# dmx_splitter.net
KiCad netlist of a schematic drawn in EAGLE
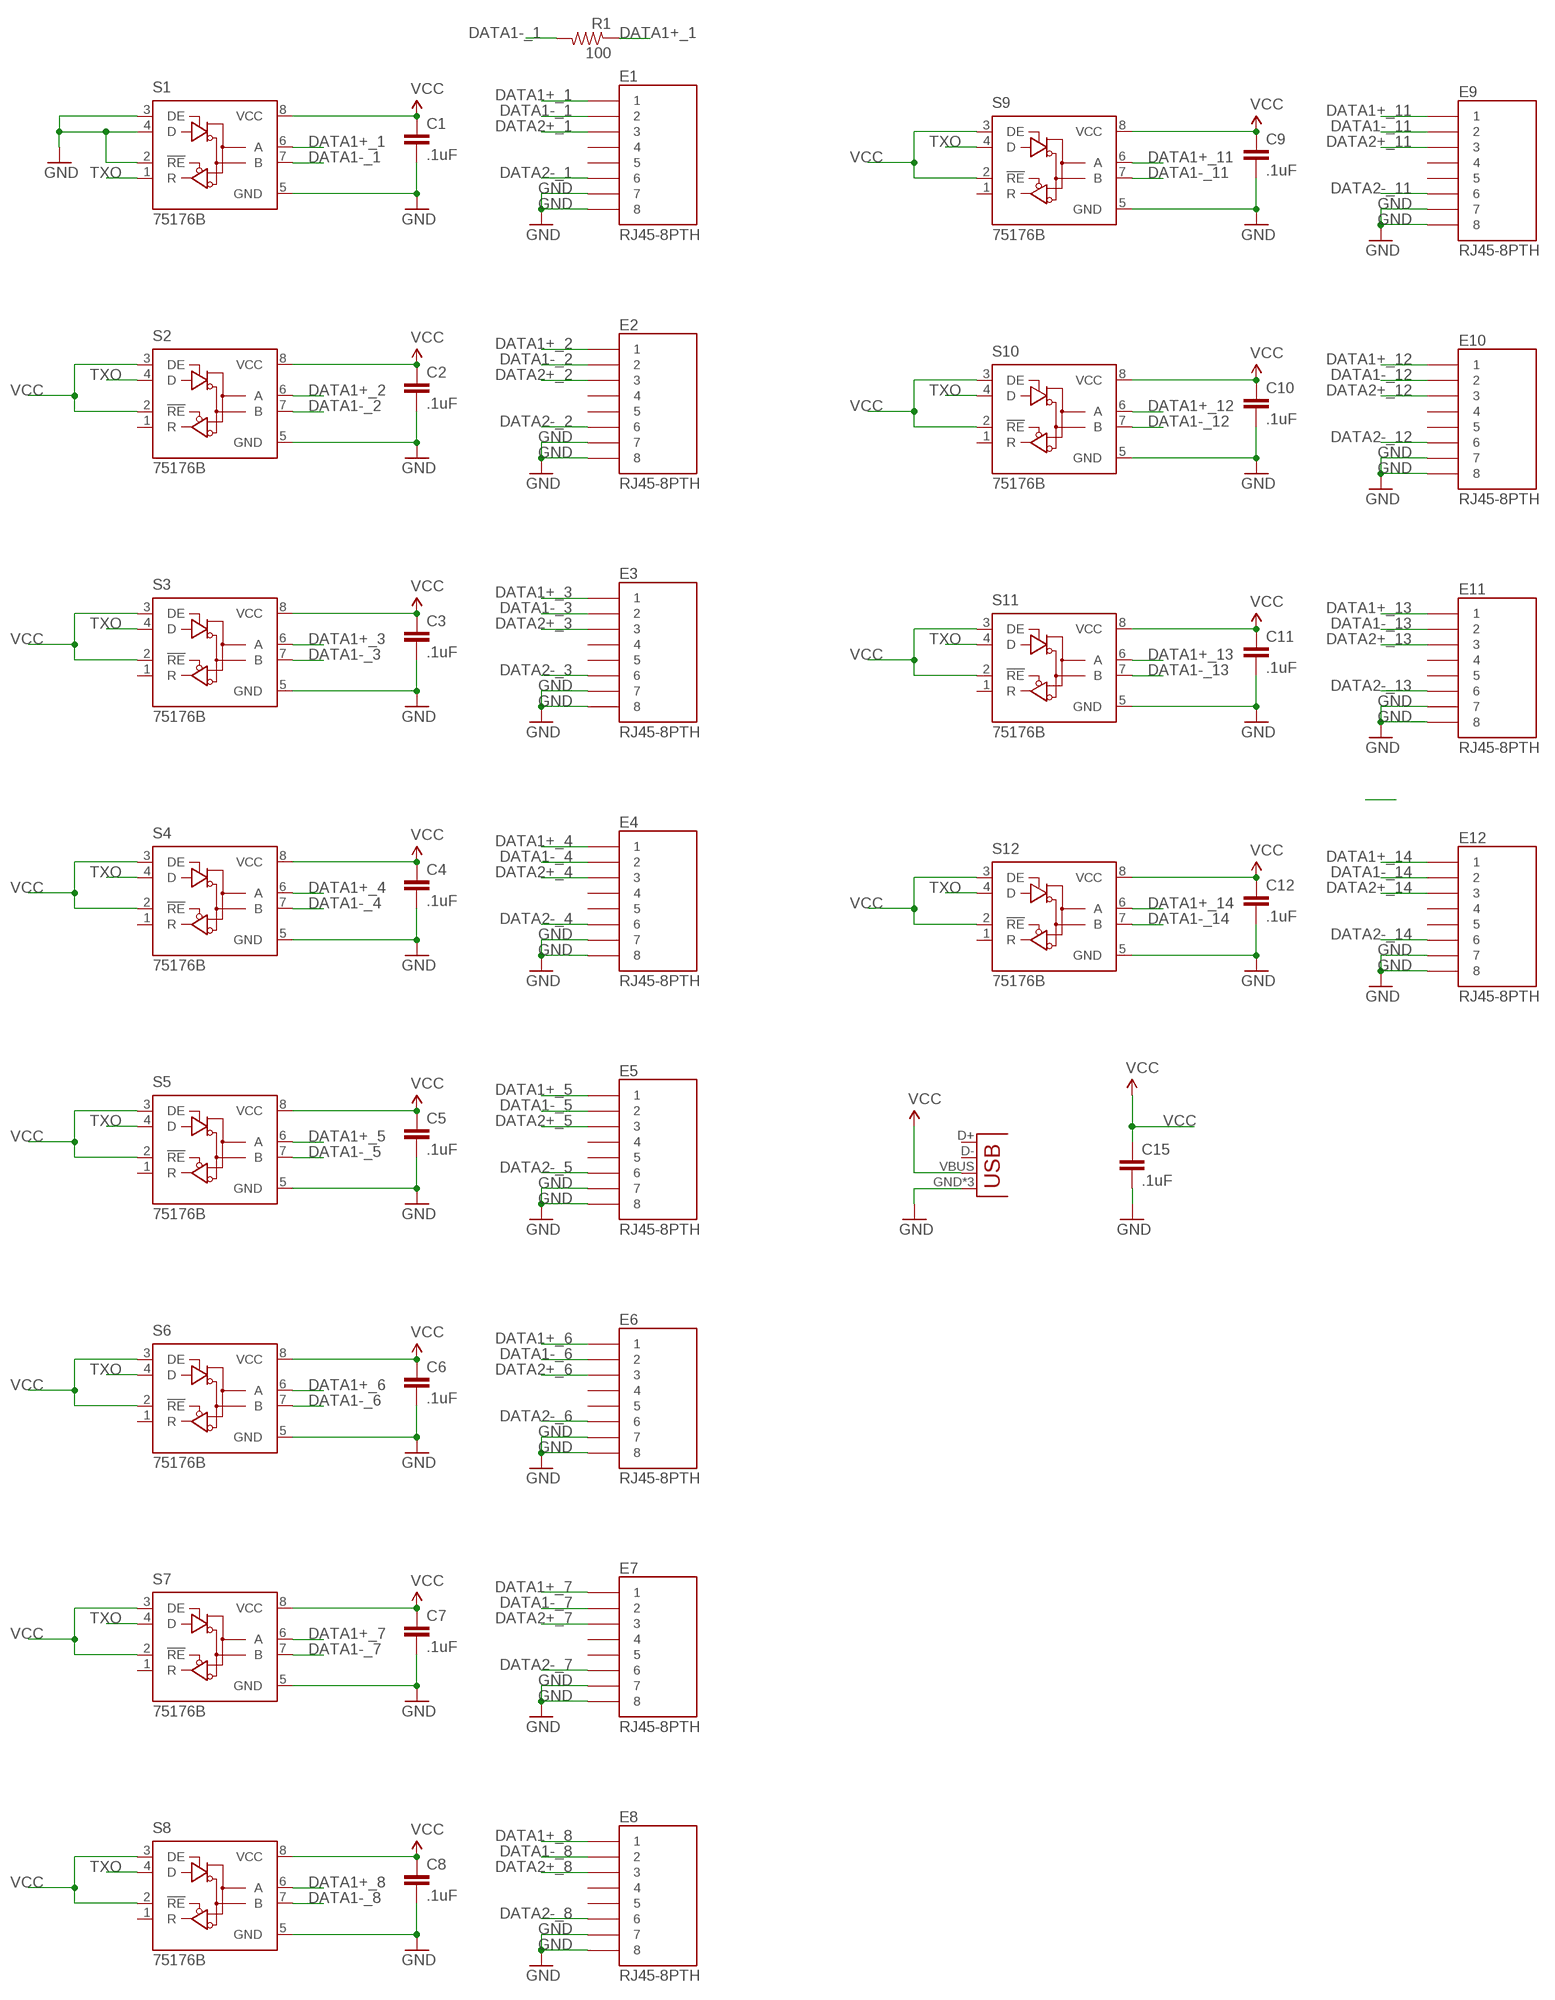
[diagram p0: schematic, sheet 1]

(export (version "E")
  (design (tool "Eeschema 10.0.6"))
  (components
    (comp (ref "C1")
      (value ".1uF")
      (footprint "eagle-import:0402-CAP")
      (libsource (lib "eagle-import") (part "CAP0402-CAP"))
    )
    (comp (ref "C2")
      (value ".1uF")
      (footprint "eagle-import:0402-CAP")
      (libsource (lib "eagle-import") (part "CAP0402-CAP"))
    )
    (comp (ref "C3")
      (value ".1uF")
      (footprint "eagle-import:0402-CAP")
      (libsource (lib "eagle-import") (part "CAP0402-CAP"))
    )
    (comp (ref "C4")
      (value ".1uF")
      (footprint "eagle-import:0402-CAP")
      (libsource (lib "eagle-import") (part "CAP0402-CAP"))
    )
    (comp (ref "C5")
      (value ".1uF")
      (footprint "eagle-import:0402-CAP")
      (libsource (lib "eagle-import") (part "CAP0402-CAP"))
    )
    (comp (ref "C6")
      (value ".1uF")
      (footprint "eagle-import:0402-CAP")
      (libsource (lib "eagle-import") (part "CAP0402-CAP"))
    )
    (comp (ref "C7")
      (value ".1uF")
      (footprint "eagle-import:0402-CAP")
      (libsource (lib "eagle-import") (part "CAP0402-CAP"))
    )
    (comp (ref "C8")
      (value ".1uF")
      (footprint "eagle-import:0402-CAP")
      (libsource (lib "eagle-import") (part "CAP0402-CAP"))
    )
    (comp (ref "C9")
      (value ".1uF")
      (footprint "eagle-import:0402-CAP")
      (libsource (lib "eagle-import") (part "CAP0402-CAP"))
    )
    (comp (ref "C10")
      (value ".1uF")
      (footprint "eagle-import:0402-CAP")
      (libsource (lib "eagle-import") (part "CAP0402-CAP"))
    )
    (comp (ref "C11")
      (value ".1uF")
      (footprint "eagle-import:0402-CAP")
      (libsource (lib "eagle-import") (part "CAP0402-CAP"))
    )
    (comp (ref "C12")
      (value ".1uF")
      (footprint "eagle-import:0402-CAP")
      (libsource (lib "eagle-import") (part "CAP0402-CAP"))
    )
    (comp (ref "C15")
      (value ".1uF")
      (footprint "eagle-import:0402-CAP")
      (libsource (lib "eagle-import") (part "CAP0402-CAP"))
    )
    (comp (ref "E1")
      (value "RJ45-8PTH")
      (footprint "eagle-import:RJ45-8")
      (libsource (lib "eagle-import") (part "RJ45-8PTH"))
    )
    (comp (ref "E2")
      (value "RJ45-8PTH")
      (footprint "eagle-import:RJ45-8")
      (libsource (lib "eagle-import") (part "RJ45-8PTH"))
    )
    (comp (ref "E3")
      (value "RJ45-8PTH")
      (footprint "eagle-import:RJ45-8")
      (libsource (lib "eagle-import") (part "RJ45-8PTH"))
    )
    (comp (ref "E4")
      (value "RJ45-8PTH")
      (footprint "eagle-import:RJ45-8")
      (libsource (lib "eagle-import") (part "RJ45-8PTH"))
    )
    (comp (ref "E5")
      (value "RJ45-8PTH")
      (footprint "eagle-import:RJ45-8")
      (libsource (lib "eagle-import") (part "RJ45-8PTH"))
    )
    (comp (ref "E6")
      (value "RJ45-8PTH")
      (footprint "eagle-import:RJ45-8")
      (libsource (lib "eagle-import") (part "RJ45-8PTH"))
    )
    (comp (ref "E7")
      (value "RJ45-8PTH")
      (footprint "eagle-import:RJ45-8")
      (libsource (lib "eagle-import") (part "RJ45-8PTH"))
    )
    (comp (ref "E8")
      (value "RJ45-8PTH")
      (footprint "eagle-import:RJ45-8")
      (libsource (lib "eagle-import") (part "RJ45-8PTH"))
    )
    (comp (ref "E9")
      (value "RJ45-8PTH")
      (footprint "eagle-import:RJ45-8")
      (libsource (lib "eagle-import") (part "RJ45-8PTH"))
    )
    (comp (ref "E10")
      (value "RJ45-8PTH")
      (footprint "eagle-import:RJ45-8")
      (libsource (lib "eagle-import") (part "RJ45-8PTH"))
    )
    (comp (ref "E11")
      (value "RJ45-8PTH")
      (footprint "eagle-import:RJ45-8")
      (libsource (lib "eagle-import") (part "RJ45-8PTH"))
    )
    (comp (ref "E12")
      (value "RJ45-8PTH")
      (footprint "eagle-import:RJ45-8")
      (libsource (lib "eagle-import") (part "RJ45-8PTH"))
    )
    (comp (ref "JP1")
      (value "USB-MICROB")
      (footprint "eagle-import:USB-MICROB")
      (libsource (lib "eagle-import") (part "USB-MICROB"))
    )
    (comp (ref "R1")
      (value "100")
      (footprint "eagle-import:1206")
      (libsource (lib "eagle-import") (part "RESISTOR1206"))
    )
    (comp (ref "S1")
      (value "75176B")
      (footprint "eagle-import:D_R-PDSO-G8")
      (libsource (lib "eagle-import") (part "75176B"))
    )
    (comp (ref "S2")
      (value "75176B")
      (footprint "eagle-import:D_R-PDSO-G8")
      (libsource (lib "eagle-import") (part "75176B"))
    )
    (comp (ref "S3")
      (value "75176B")
      (footprint "eagle-import:D_R-PDSO-G8")
      (libsource (lib "eagle-import") (part "75176B"))
    )
    (comp (ref "S4")
      (value "75176B")
      (footprint "eagle-import:D_R-PDSO-G8")
      (libsource (lib "eagle-import") (part "75176B"))
    )
    (comp (ref "S5")
      (value "75176B")
      (footprint "eagle-import:D_R-PDSO-G8")
      (libsource (lib "eagle-import") (part "75176B"))
    )
    (comp (ref "S6")
      (value "75176B")
      (footprint "eagle-import:D_R-PDSO-G8")
      (libsource (lib "eagle-import") (part "75176B"))
    )
    (comp (ref "S7")
      (value "75176B")
      (footprint "eagle-import:D_R-PDSO-G8")
      (libsource (lib "eagle-import") (part "75176B"))
    )
    (comp (ref "S8")
      (value "75176B")
      (footprint "eagle-import:D_R-PDSO-G8")
      (libsource (lib "eagle-import") (part "75176B"))
    )
    (comp (ref "S9")
      (value "75176B")
      (footprint "eagle-import:D_R-PDSO-G8")
      (libsource (lib "eagle-import") (part "75176B"))
    )
    (comp (ref "S10")
      (value "75176B")
      (footprint "eagle-import:D_R-PDSO-G8")
      (libsource (lib "eagle-import") (part "75176B"))
    )
    (comp (ref "S11")
      (value "75176B")
      (footprint "eagle-import:D_R-PDSO-G8")
      (libsource (lib "eagle-import") (part "75176B"))
    )
    (comp (ref "S12")
      (value "75176B")
      (footprint "eagle-import:D_R-PDSO-G8")
      (libsource (lib "eagle-import") (part "75176B"))
    )
  )
  (nets
    (net (code "1") (name "/DATA1+_1") (class "Default")
      (node (ref "E1") (pin "1") (pinfunction "1_1") (pintype "bidirectional"))
      (node (ref "R1") (pin "1") (pinfunction "1_1") (pintype "passive"))
      (node (ref "S1") (pin "6") (pinfunction "A_6") (pintype "output"))
    )
    (net (code "2") (name "/DATA1+_2") (class "Default")
      (node (ref "E2") (pin "1") (pinfunction "1_1") (pintype "bidirectional"))
      (node (ref "S2") (pin "6") (pinfunction "A_6") (pintype "output"))
    )
    (net (code "3") (name "/DATA1+_3") (class "Default")
      (node (ref "E3") (pin "1") (pinfunction "1_1") (pintype "bidirectional"))
      (node (ref "S3") (pin "6") (pinfunction "A_6") (pintype "output"))
    )
    (net (code "4") (name "/DATA1+_4") (class "Default")
      (node (ref "E4") (pin "1") (pinfunction "1_1") (pintype "bidirectional"))
      (node (ref "S4") (pin "6") (pinfunction "A_6") (pintype "output"))
    )
    (net (code "5") (name "/DATA1+_5") (class "Default")
      (node (ref "E5") (pin "1") (pinfunction "1_1") (pintype "bidirectional"))
      (node (ref "S5") (pin "6") (pinfunction "A_6") (pintype "output"))
    )
    (net (code "6") (name "/DATA1+_6") (class "Default")
      (node (ref "E6") (pin "1") (pinfunction "1_1") (pintype "bidirectional"))
      (node (ref "S6") (pin "6") (pinfunction "A_6") (pintype "output"))
    )
    (net (code "7") (name "/DATA1+_7") (class "Default")
      (node (ref "E7") (pin "1") (pinfunction "1_1") (pintype "bidirectional"))
      (node (ref "S7") (pin "6") (pinfunction "A_6") (pintype "output"))
    )
    (net (code "8") (name "/DATA1+_8") (class "Default")
      (node (ref "E8") (pin "1") (pinfunction "1_1") (pintype "bidirectional"))
      (node (ref "S8") (pin "6") (pinfunction "A_6") (pintype "output"))
    )
    (net (code "9") (name "/DATA1+_11") (class "Default")
      (node (ref "E9") (pin "1") (pinfunction "1_1") (pintype "bidirectional"))
      (node (ref "S9") (pin "6") (pinfunction "A_6") (pintype "output"))
    )
    (net (code "10") (name "/DATA1+_12") (class "Default")
      (node (ref "E10") (pin "1") (pinfunction "1_1") (pintype "bidirectional"))
      (node (ref "S10") (pin "6") (pinfunction "A_6") (pintype "output"))
    )
    (net (code "11") (name "/DATA1+_13") (class "Default")
      (node (ref "E11") (pin "1") (pinfunction "1_1") (pintype "bidirectional"))
      (node (ref "S11") (pin "6") (pinfunction "A_6") (pintype "output"))
    )
    (net (code "12") (name "/DATA1+_14") (class "Default")
      (node (ref "E12") (pin "1") (pinfunction "1_1") (pintype "bidirectional"))
      (node (ref "S12") (pin "6") (pinfunction "A_6") (pintype "output"))
    )
    (net (code "13") (name "/DATA1-_1") (class "Default")
      (node (ref "E1") (pin "2") (pinfunction "2_2") (pintype "bidirectional"))
      (node (ref "R1") (pin "2") (pinfunction "2_2") (pintype "passive"))
      (node (ref "S1") (pin "7") (pinfunction "B_7") (pintype "output"))
    )
    (net (code "14") (name "/DATA1-_2") (class "Default")
      (node (ref "E2") (pin "2") (pinfunction "2_2") (pintype "bidirectional"))
      (node (ref "S2") (pin "7") (pinfunction "B_7") (pintype "output"))
    )
    (net (code "15") (name "/DATA1-_3") (class "Default")
      (node (ref "E3") (pin "2") (pinfunction "2_2") (pintype "bidirectional"))
      (node (ref "S3") (pin "7") (pinfunction "B_7") (pintype "output"))
    )
    (net (code "16") (name "/DATA1-_4") (class "Default")
      (node (ref "E4") (pin "2") (pinfunction "2_2") (pintype "bidirectional"))
      (node (ref "S4") (pin "7") (pinfunction "B_7") (pintype "output"))
    )
    (net (code "17") (name "/DATA1-_5") (class "Default")
      (node (ref "E5") (pin "2") (pinfunction "2_2") (pintype "bidirectional"))
      (node (ref "S5") (pin "7") (pinfunction "B_7") (pintype "output"))
    )
    (net (code "18") (name "/DATA1-_6") (class "Default")
      (node (ref "E6") (pin "2") (pinfunction "2_2") (pintype "bidirectional"))
      (node (ref "S6") (pin "7") (pinfunction "B_7") (pintype "output"))
    )
    (net (code "19") (name "/DATA1-_7") (class "Default")
      (node (ref "E7") (pin "2") (pinfunction "2_2") (pintype "bidirectional"))
      (node (ref "S7") (pin "7") (pinfunction "B_7") (pintype "output"))
    )
    (net (code "20") (name "/DATA1-_8") (class "Default")
      (node (ref "E8") (pin "2") (pinfunction "2_2") (pintype "bidirectional"))
      (node (ref "S8") (pin "7") (pinfunction "B_7") (pintype "output"))
    )
    (net (code "21") (name "/DATA1-_11") (class "Default")
      (node (ref "E9") (pin "2") (pinfunction "2_2") (pintype "bidirectional"))
      (node (ref "S9") (pin "7") (pinfunction "B_7") (pintype "output"))
    )
    (net (code "22") (name "/DATA1-_12") (class "Default")
      (node (ref "E10") (pin "2") (pinfunction "2_2") (pintype "bidirectional"))
      (node (ref "S10") (pin "7") (pinfunction "B_7") (pintype "output"))
    )
    (net (code "23") (name "/DATA1-_13") (class "Default")
      (node (ref "E11") (pin "2") (pinfunction "2_2") (pintype "bidirectional"))
      (node (ref "S11") (pin "7") (pinfunction "B_7") (pintype "output"))
    )
    (net (code "24") (name "/DATA1-_14") (class "Default")
      (node (ref "E12") (pin "2") (pinfunction "2_2") (pintype "bidirectional"))
      (node (ref "S12") (pin "7") (pinfunction "B_7") (pintype "output"))
    )
    (net (code "25") (name "/DATA2+_1") (class "Default")
      (node (ref "E1") (pin "3") (pinfunction "3_3") (pintype "bidirectional"))
    )
    (net (code "26") (name "/DATA2+_2") (class "Default")
      (node (ref "E2") (pin "3") (pinfunction "3_3") (pintype "bidirectional"))
    )
    (net (code "27") (name "/DATA2+_3") (class "Default")
      (node (ref "E3") (pin "3") (pinfunction "3_3") (pintype "bidirectional"))
    )
    (net (code "28") (name "/DATA2+_4") (class "Default")
      (node (ref "E4") (pin "3") (pinfunction "3_3") (pintype "bidirectional"))
    )
    (net (code "29") (name "/DATA2+_5") (class "Default")
      (node (ref "E5") (pin "3") (pinfunction "3_3") (pintype "bidirectional"))
    )
    (net (code "30") (name "/DATA2+_6") (class "Default")
      (node (ref "E6") (pin "3") (pinfunction "3_3") (pintype "bidirectional"))
    )
    (net (code "31") (name "/DATA2+_7") (class "Default")
      (node (ref "E7") (pin "3") (pinfunction "3_3") (pintype "bidirectional"))
    )
    (net (code "32") (name "/DATA2+_8") (class "Default")
      (node (ref "E8") (pin "3") (pinfunction "3_3") (pintype "bidirectional"))
    )
    (net (code "33") (name "/DATA2+_11") (class "Default")
      (node (ref "E9") (pin "3") (pinfunction "3_3") (pintype "bidirectional"))
    )
    (net (code "34") (name "/DATA2+_12") (class "Default")
      (node (ref "E10") (pin "3") (pinfunction "3_3") (pintype "bidirectional"))
    )
    (net (code "35") (name "/DATA2+_13") (class "Default")
      (node (ref "E11") (pin "3") (pinfunction "3_3") (pintype "bidirectional"))
    )
    (net (code "36") (name "/DATA2+_14") (class "Default")
      (node (ref "E12") (pin "3") (pinfunction "3_3") (pintype "bidirectional"))
    )
    (net (code "37") (name "/DATA2-_1") (class "Default")
      (node (ref "E1") (pin "6") (pinfunction "6_6") (pintype "bidirectional"))
    )
    (net (code "38") (name "/DATA2-_2") (class "Default")
      (node (ref "E2") (pin "6") (pinfunction "6_6") (pintype "bidirectional"))
    )
    (net (code "39") (name "/DATA2-_3") (class "Default")
      (node (ref "E3") (pin "6") (pinfunction "6_6") (pintype "bidirectional"))
    )
    (net (code "40") (name "/DATA2-_4") (class "Default")
      (node (ref "E4") (pin "6") (pinfunction "6_6") (pintype "bidirectional"))
    )
    (net (code "41") (name "/DATA2-_5") (class "Default")
      (node (ref "E5") (pin "6") (pinfunction "6_6") (pintype "bidirectional"))
    )
    (net (code "42") (name "/DATA2-_6") (class "Default")
      (node (ref "E6") (pin "6") (pinfunction "6_6") (pintype "bidirectional"))
    )
    (net (code "43") (name "/DATA2-_7") (class "Default")
      (node (ref "E7") (pin "6") (pinfunction "6_6") (pintype "bidirectional"))
    )
    (net (code "44") (name "/DATA2-_8") (class "Default")
      (node (ref "E8") (pin "6") (pinfunction "6_6") (pintype "bidirectional"))
    )
    (net (code "45") (name "/DATA2-_11") (class "Default")
      (node (ref "E9") (pin "6") (pinfunction "6_6") (pintype "bidirectional"))
    )
    (net (code "46") (name "/DATA2-_12") (class "Default")
      (node (ref "E10") (pin "6") (pinfunction "6_6") (pintype "bidirectional"))
    )
    (net (code "47") (name "/DATA2-_13") (class "Default")
      (node (ref "E11") (pin "6") (pinfunction "6_6") (pintype "bidirectional"))
    )
    (net (code "48") (name "/DATA2-_14") (class "Default")
      (node (ref "E12") (pin "6") (pinfunction "6_6") (pintype "bidirectional"))
    )
    (net (code "49") (name "/TXO") (class "Default")
      (node (ref "S1") (pin "1") (pinfunction "R_1") (pintype "input"))
      (node (ref "S10") (pin "4") (pinfunction "D_4") (pintype "input"))
      (node (ref "S11") (pin "4") (pinfunction "D_4") (pintype "input"))
      (node (ref "S12") (pin "4") (pinfunction "D_4") (pintype "input"))
      (node (ref "S2") (pin "4") (pinfunction "D_4") (pintype "input"))
      (node (ref "S3") (pin "4") (pinfunction "D_4") (pintype "input"))
      (node (ref "S4") (pin "4") (pinfunction "D_4") (pintype "input"))
      (node (ref "S5") (pin "4") (pinfunction "D_4") (pintype "input"))
      (node (ref "S6") (pin "4") (pinfunction "D_4") (pintype "input"))
      (node (ref "S7") (pin "4") (pinfunction "D_4") (pintype "input"))
      (node (ref "S8") (pin "4") (pinfunction "D_4") (pintype "input"))
      (node (ref "S9") (pin "4") (pinfunction "D_4") (pintype "input"))
    )
    (net (code "50") (name "GND") (class "Default")
      (node (ref "C1") (pin "2") (pinfunction "2_2") (pintype "passive"))
      (node (ref "C10") (pin "2") (pinfunction "2_2") (pintype "passive"))
      (node (ref "C11") (pin "2") (pinfunction "2_2") (pintype "passive"))
      (node (ref "C12") (pin "2") (pinfunction "2_2") (pintype "passive"))
      (node (ref "C15") (pin "2") (pinfunction "2_2") (pintype "passive"))
      (node (ref "C2") (pin "2") (pinfunction "2_2") (pintype "passive"))
      (node (ref "C3") (pin "2") (pinfunction "2_2") (pintype "passive"))
      (node (ref "C4") (pin "2") (pinfunction "2_2") (pintype "passive"))
      (node (ref "C5") (pin "2") (pinfunction "2_2") (pintype "passive"))
      (node (ref "C6") (pin "2") (pinfunction "2_2") (pintype "passive"))
      (node (ref "C7") (pin "2") (pinfunction "2_2") (pintype "passive"))
      (node (ref "C8") (pin "2") (pinfunction "2_2") (pintype "passive"))
      (node (ref "C9") (pin "2") (pinfunction "2_2") (pintype "passive"))
      (node (ref "E1") (pin "7") (pinfunction "7_7") (pintype "bidirectional"))
      (node (ref "E1") (pin "8") (pinfunction "8_8") (pintype "bidirectional"))
      (node (ref "E10") (pin "7") (pinfunction "7_7") (pintype "bidirectional"))
      (node (ref "E10") (pin "8") (pinfunction "8_8") (pintype "bidirectional"))
      (node (ref "E11") (pin "7") (pinfunction "7_7") (pintype "bidirectional"))
      (node (ref "E11") (pin "8") (pinfunction "8_8") (pintype "bidirectional"))
      (node (ref "E12") (pin "7") (pinfunction "7_7") (pintype "bidirectional"))
      (node (ref "E12") (pin "8") (pinfunction "8_8") (pintype "bidirectional"))
      (node (ref "E2") (pin "7") (pinfunction "7_7") (pintype "bidirectional"))
      (node (ref "E2") (pin "8") (pinfunction "8_8") (pintype "bidirectional"))
      (node (ref "E3") (pin "7") (pinfunction "7_7") (pintype "bidirectional"))
      (node (ref "E3") (pin "8") (pinfunction "8_8") (pintype "bidirectional"))
      (node (ref "E4") (pin "7") (pinfunction "7_7") (pintype "bidirectional"))
      (node (ref "E4") (pin "8") (pinfunction "8_8") (pintype "bidirectional"))
      (node (ref "E5") (pin "7") (pinfunction "7_7") (pintype "bidirectional"))
      (node (ref "E5") (pin "8") (pinfunction "8_8") (pintype "bidirectional"))
      (node (ref "E6") (pin "7") (pinfunction "7_7") (pintype "bidirectional"))
      (node (ref "E6") (pin "8") (pinfunction "8_8") (pintype "bidirectional"))
      (node (ref "E7") (pin "7") (pinfunction "7_7") (pintype "bidirectional"))
      (node (ref "E7") (pin "8") (pinfunction "8_8") (pintype "bidirectional"))
      (node (ref "E8") (pin "7") (pinfunction "7_7") (pintype "bidirectional"))
      (node (ref "E8") (pin "8") (pinfunction "8_8") (pintype "bidirectional"))
      (node (ref "E9") (pin "7") (pinfunction "7_7") (pintype "bidirectional"))
      (node (ref "E9") (pin "8") (pinfunction "8_8") (pintype "bidirectional"))
      (node (ref "JP1") (pin "GND") (pinfunction "GND_GND") (pintype "bidirectional"))
      (node (ref "JP1") (pin "MT1") (pinfunction "GND_MT1") (pintype "bidirectional"))
      (node (ref "JP1") (pin "MT2") (pinfunction "GND_MT2") (pintype "bidirectional"))
      (node (ref "S1") (pin "2") (pinfunction "~{RE}_2") (pintype "input"))
      (node (ref "S1") (pin "3") (pinfunction "DE_3") (pintype "input"))
      (node (ref "S1") (pin "4") (pinfunction "D_4") (pintype "input"))
      (node (ref "S1") (pin "5") (pinfunction "GND_5") (pintype "power_in"))
      (node (ref "S10") (pin "5") (pinfunction "GND_5") (pintype "power_in"))
      (node (ref "S11") (pin "5") (pinfunction "GND_5") (pintype "power_in"))
      (node (ref "S12") (pin "5") (pinfunction "GND_5") (pintype "power_in"))
      (node (ref "S2") (pin "5") (pinfunction "GND_5") (pintype "power_in"))
      (node (ref "S3") (pin "5") (pinfunction "GND_5") (pintype "power_in"))
      (node (ref "S4") (pin "5") (pinfunction "GND_5") (pintype "power_in"))
      (node (ref "S5") (pin "5") (pinfunction "GND_5") (pintype "power_in"))
      (node (ref "S6") (pin "5") (pinfunction "GND_5") (pintype "power_in"))
      (node (ref "S7") (pin "5") (pinfunction "GND_5") (pintype "power_in"))
      (node (ref "S8") (pin "5") (pinfunction "GND_5") (pintype "power_in"))
      (node (ref "S9") (pin "5") (pinfunction "GND_5") (pintype "power_in"))
    )
    (net (code "51") (name "VCC") (class "Default")
      (node (ref "C1") (pin "1") (pinfunction "1_1") (pintype "passive"))
      (node (ref "C10") (pin "1") (pinfunction "1_1") (pintype "passive"))
      (node (ref "C11") (pin "1") (pinfunction "1_1") (pintype "passive"))
      (node (ref "C12") (pin "1") (pinfunction "1_1") (pintype "passive"))
      (node (ref "C15") (pin "1") (pinfunction "1_1") (pintype "passive"))
      (node (ref "C2") (pin "1") (pinfunction "1_1") (pintype "passive"))
      (node (ref "C3") (pin "1") (pinfunction "1_1") (pintype "passive"))
      (node (ref "C4") (pin "1") (pinfunction "1_1") (pintype "passive"))
      (node (ref "C5") (pin "1") (pinfunction "1_1") (pintype "passive"))
      (node (ref "C6") (pin "1") (pinfunction "1_1") (pintype "passive"))
      (node (ref "C7") (pin "1") (pinfunction "1_1") (pintype "passive"))
      (node (ref "C8") (pin "1") (pinfunction "1_1") (pintype "passive"))
      (node (ref "C9") (pin "1") (pinfunction "1_1") (pintype "passive"))
      (node (ref "JP1") (pin "VBUS") (pinfunction "VBUS_VBUS") (pintype "bidirectional"))
      (node (ref "S1") (pin "8") (pinfunction "VCC_8") (pintype "power_in"))
      (node (ref "S10") (pin "2") (pinfunction "~{RE}_2") (pintype "input"))
      (node (ref "S10") (pin "3") (pinfunction "DE_3") (pintype "input"))
      (node (ref "S10") (pin "8") (pinfunction "VCC_8") (pintype "power_in"))
      (node (ref "S11") (pin "2") (pinfunction "~{RE}_2") (pintype "input"))
      (node (ref "S11") (pin "3") (pinfunction "DE_3") (pintype "input"))
      (node (ref "S11") (pin "8") (pinfunction "VCC_8") (pintype "power_in"))
      (node (ref "S12") (pin "2") (pinfunction "~{RE}_2") (pintype "input"))
      (node (ref "S12") (pin "3") (pinfunction "DE_3") (pintype "input"))
      (node (ref "S12") (pin "8") (pinfunction "VCC_8") (pintype "power_in"))
      (node (ref "S2") (pin "2") (pinfunction "~{RE}_2") (pintype "input"))
      (node (ref "S2") (pin "3") (pinfunction "DE_3") (pintype "input"))
      (node (ref "S2") (pin "8") (pinfunction "VCC_8") (pintype "power_in"))
      (node (ref "S3") (pin "2") (pinfunction "~{RE}_2") (pintype "input"))
      (node (ref "S3") (pin "3") (pinfunction "DE_3") (pintype "input"))
      (node (ref "S3") (pin "8") (pinfunction "VCC_8") (pintype "power_in"))
      (node (ref "S4") (pin "2") (pinfunction "~{RE}_2") (pintype "input"))
      (node (ref "S4") (pin "3") (pinfunction "DE_3") (pintype "input"))
      (node (ref "S4") (pin "8") (pinfunction "VCC_8") (pintype "power_in"))
      (node (ref "S5") (pin "2") (pinfunction "~{RE}_2") (pintype "input"))
      (node (ref "S5") (pin "3") (pinfunction "DE_3") (pintype "input"))
      (node (ref "S5") (pin "8") (pinfunction "VCC_8") (pintype "power_in"))
      (node (ref "S6") (pin "2") (pinfunction "~{RE}_2") (pintype "input"))
      (node (ref "S6") (pin "3") (pinfunction "DE_3") (pintype "input"))
      (node (ref "S6") (pin "8") (pinfunction "VCC_8") (pintype "power_in"))
      (node (ref "S7") (pin "2") (pinfunction "~{RE}_2") (pintype "input"))
      (node (ref "S7") (pin "3") (pinfunction "DE_3") (pintype "input"))
      (node (ref "S7") (pin "8") (pinfunction "VCC_8") (pintype "power_in"))
      (node (ref "S8") (pin "2") (pinfunction "~{RE}_2") (pintype "input"))
      (node (ref "S8") (pin "3") (pinfunction "DE_3") (pintype "input"))
      (node (ref "S8") (pin "8") (pinfunction "VCC_8") (pintype "power_in"))
      (node (ref "S9") (pin "2") (pinfunction "~{RE}_2") (pintype "input"))
      (node (ref "S9") (pin "3") (pinfunction "DE_3") (pintype "input"))
      (node (ref "S9") (pin "8") (pinfunction "VCC_8") (pintype "power_in"))
    )
    (net (code "52") (name "unconnected-(E1-Pad4)") (class "Default")
      (node (ref "E1") (pin "4") (pinfunction "4_4") (pintype "bidirectional"))
    )
    (net (code "53") (name "unconnected-(E1-Pad5)") (class "Default")
      (node (ref "E1") (pin "5") (pinfunction "5_5") (pintype "bidirectional"))
    )
    (net (code "54") (name "unconnected-(E2-Pad4)") (class "Default")
      (node (ref "E2") (pin "4") (pinfunction "4_4") (pintype "bidirectional"))
    )
    (net (code "55") (name "unconnected-(E2-Pad5)") (class "Default")
      (node (ref "E2") (pin "5") (pinfunction "5_5") (pintype "bidirectional"))
    )
    (net (code "56") (name "unconnected-(E3-Pad4)") (class "Default")
      (node (ref "E3") (pin "4") (pinfunction "4_4") (pintype "bidirectional"))
    )
    (net (code "57") (name "unconnected-(E3-Pad5)") (class "Default")
      (node (ref "E3") (pin "5") (pinfunction "5_5") (pintype "bidirectional"))
    )
    (net (code "58") (name "unconnected-(E4-Pad4)") (class "Default")
      (node (ref "E4") (pin "4") (pinfunction "4_4") (pintype "bidirectional"))
    )
    (net (code "59") (name "unconnected-(E4-Pad5)") (class "Default")
      (node (ref "E4") (pin "5") (pinfunction "5_5") (pintype "bidirectional"))
    )
    (net (code "60") (name "unconnected-(E5-Pad4)") (class "Default")
      (node (ref "E5") (pin "4") (pinfunction "4_4") (pintype "bidirectional"))
    )
    (net (code "61") (name "unconnected-(E5-Pad5)") (class "Default")
      (node (ref "E5") (pin "5") (pinfunction "5_5") (pintype "bidirectional"))
    )
    (net (code "62") (name "unconnected-(E6-Pad4)") (class "Default")
      (node (ref "E6") (pin "4") (pinfunction "4_4") (pintype "bidirectional"))
    )
    (net (code "63") (name "unconnected-(E6-Pad5)") (class "Default")
      (node (ref "E6") (pin "5") (pinfunction "5_5") (pintype "bidirectional"))
    )
    (net (code "64") (name "unconnected-(E7-Pad4)") (class "Default")
      (node (ref "E7") (pin "4") (pinfunction "4_4") (pintype "bidirectional"))
    )
    (net (code "65") (name "unconnected-(E7-Pad5)") (class "Default")
      (node (ref "E7") (pin "5") (pinfunction "5_5") (pintype "bidirectional"))
    )
    (net (code "66") (name "unconnected-(E8-Pad4)") (class "Default")
      (node (ref "E8") (pin "4") (pinfunction "4_4") (pintype "bidirectional"))
    )
    (net (code "67") (name "unconnected-(E8-Pad5)") (class "Default")
      (node (ref "E8") (pin "5") (pinfunction "5_5") (pintype "bidirectional"))
    )
    (net (code "68") (name "unconnected-(E9-Pad4)") (class "Default")
      (node (ref "E9") (pin "4") (pinfunction "4_4") (pintype "bidirectional"))
    )
    (net (code "69") (name "unconnected-(E9-Pad5)") (class "Default")
      (node (ref "E9") (pin "5") (pinfunction "5_5") (pintype "bidirectional"))
    )
    (net (code "70") (name "unconnected-(E10-Pad4)") (class "Default")
      (node (ref "E10") (pin "4") (pinfunction "4_4") (pintype "bidirectional"))
    )
    (net (code "71") (name "unconnected-(E10-Pad5)") (class "Default")
      (node (ref "E10") (pin "5") (pinfunction "5_5") (pintype "bidirectional"))
    )
    (net (code "72") (name "unconnected-(E11-Pad4)") (class "Default")
      (node (ref "E11") (pin "4") (pinfunction "4_4") (pintype "bidirectional"))
    )
    (net (code "73") (name "unconnected-(E11-Pad5)") (class "Default")
      (node (ref "E11") (pin "5") (pinfunction "5_5") (pintype "bidirectional"))
    )
    (net (code "74") (name "unconnected-(E12-Pad4)") (class "Default")
      (node (ref "E12") (pin "4") (pinfunction "4_4") (pintype "bidirectional"))
    )
    (net (code "75") (name "unconnected-(E12-Pad5)") (class "Default")
      (node (ref "E12") (pin "5") (pinfunction "5_5") (pintype "bidirectional"))
    )
    (net (code "76") (name "unconnected-(JP1-PadD+)") (class "Default")
      (node (ref "JP1") (pin "D+") (pinfunction "D+_D+") (pintype "bidirectional"))
    )
    (net (code "77") (name "unconnected-(JP1-PadD-)") (class "Default")
      (node (ref "JP1") (pin "D-") (pinfunction "D-_D-") (pintype "bidirectional"))
    )
    (net (code "78") (name "unconnected-(S2-R-Pad1)") (class "Default")
      (node (ref "S2") (pin "1") (pinfunction "R_1") (pintype "input"))
    )
    (net (code "79") (name "unconnected-(S3-R-Pad1)") (class "Default")
      (node (ref "S3") (pin "1") (pinfunction "R_1") (pintype "input"))
    )
    (net (code "80") (name "unconnected-(S4-R-Pad1)") (class "Default")
      (node (ref "S4") (pin "1") (pinfunction "R_1") (pintype "input"))
    )
    (net (code "81") (name "unconnected-(S5-R-Pad1)") (class "Default")
      (node (ref "S5") (pin "1") (pinfunction "R_1") (pintype "input"))
    )
    (net (code "82") (name "unconnected-(S6-R-Pad1)") (class "Default")
      (node (ref "S6") (pin "1") (pinfunction "R_1") (pintype "input"))
    )
    (net (code "83") (name "unconnected-(S7-R-Pad1)") (class "Default")
      (node (ref "S7") (pin "1") (pinfunction "R_1") (pintype "input"))
    )
    (net (code "84") (name "unconnected-(S8-R-Pad1)") (class "Default")
      (node (ref "S8") (pin "1") (pinfunction "R_1") (pintype "input"))
    )
    (net (code "85") (name "unconnected-(S9-R-Pad1)") (class "Default")
      (node (ref "S9") (pin "1") (pinfunction "R_1") (pintype "input"))
    )
    (net (code "86") (name "unconnected-(S10-R-Pad1)") (class "Default")
      (node (ref "S10") (pin "1") (pinfunction "R_1") (pintype "input"))
    )
    (net (code "87") (name "unconnected-(S11-R-Pad1)") (class "Default")
      (node (ref "S11") (pin "1") (pinfunction "R_1") (pintype "input"))
    )
    (net (code "88") (name "unconnected-(S12-R-Pad1)") (class "Default")
      (node (ref "S12") (pin "1") (pinfunction "R_1") (pintype "input"))
    )
  )
)
